# schematic.net
KiCad netlist of a schematic drawn in EasyEDA
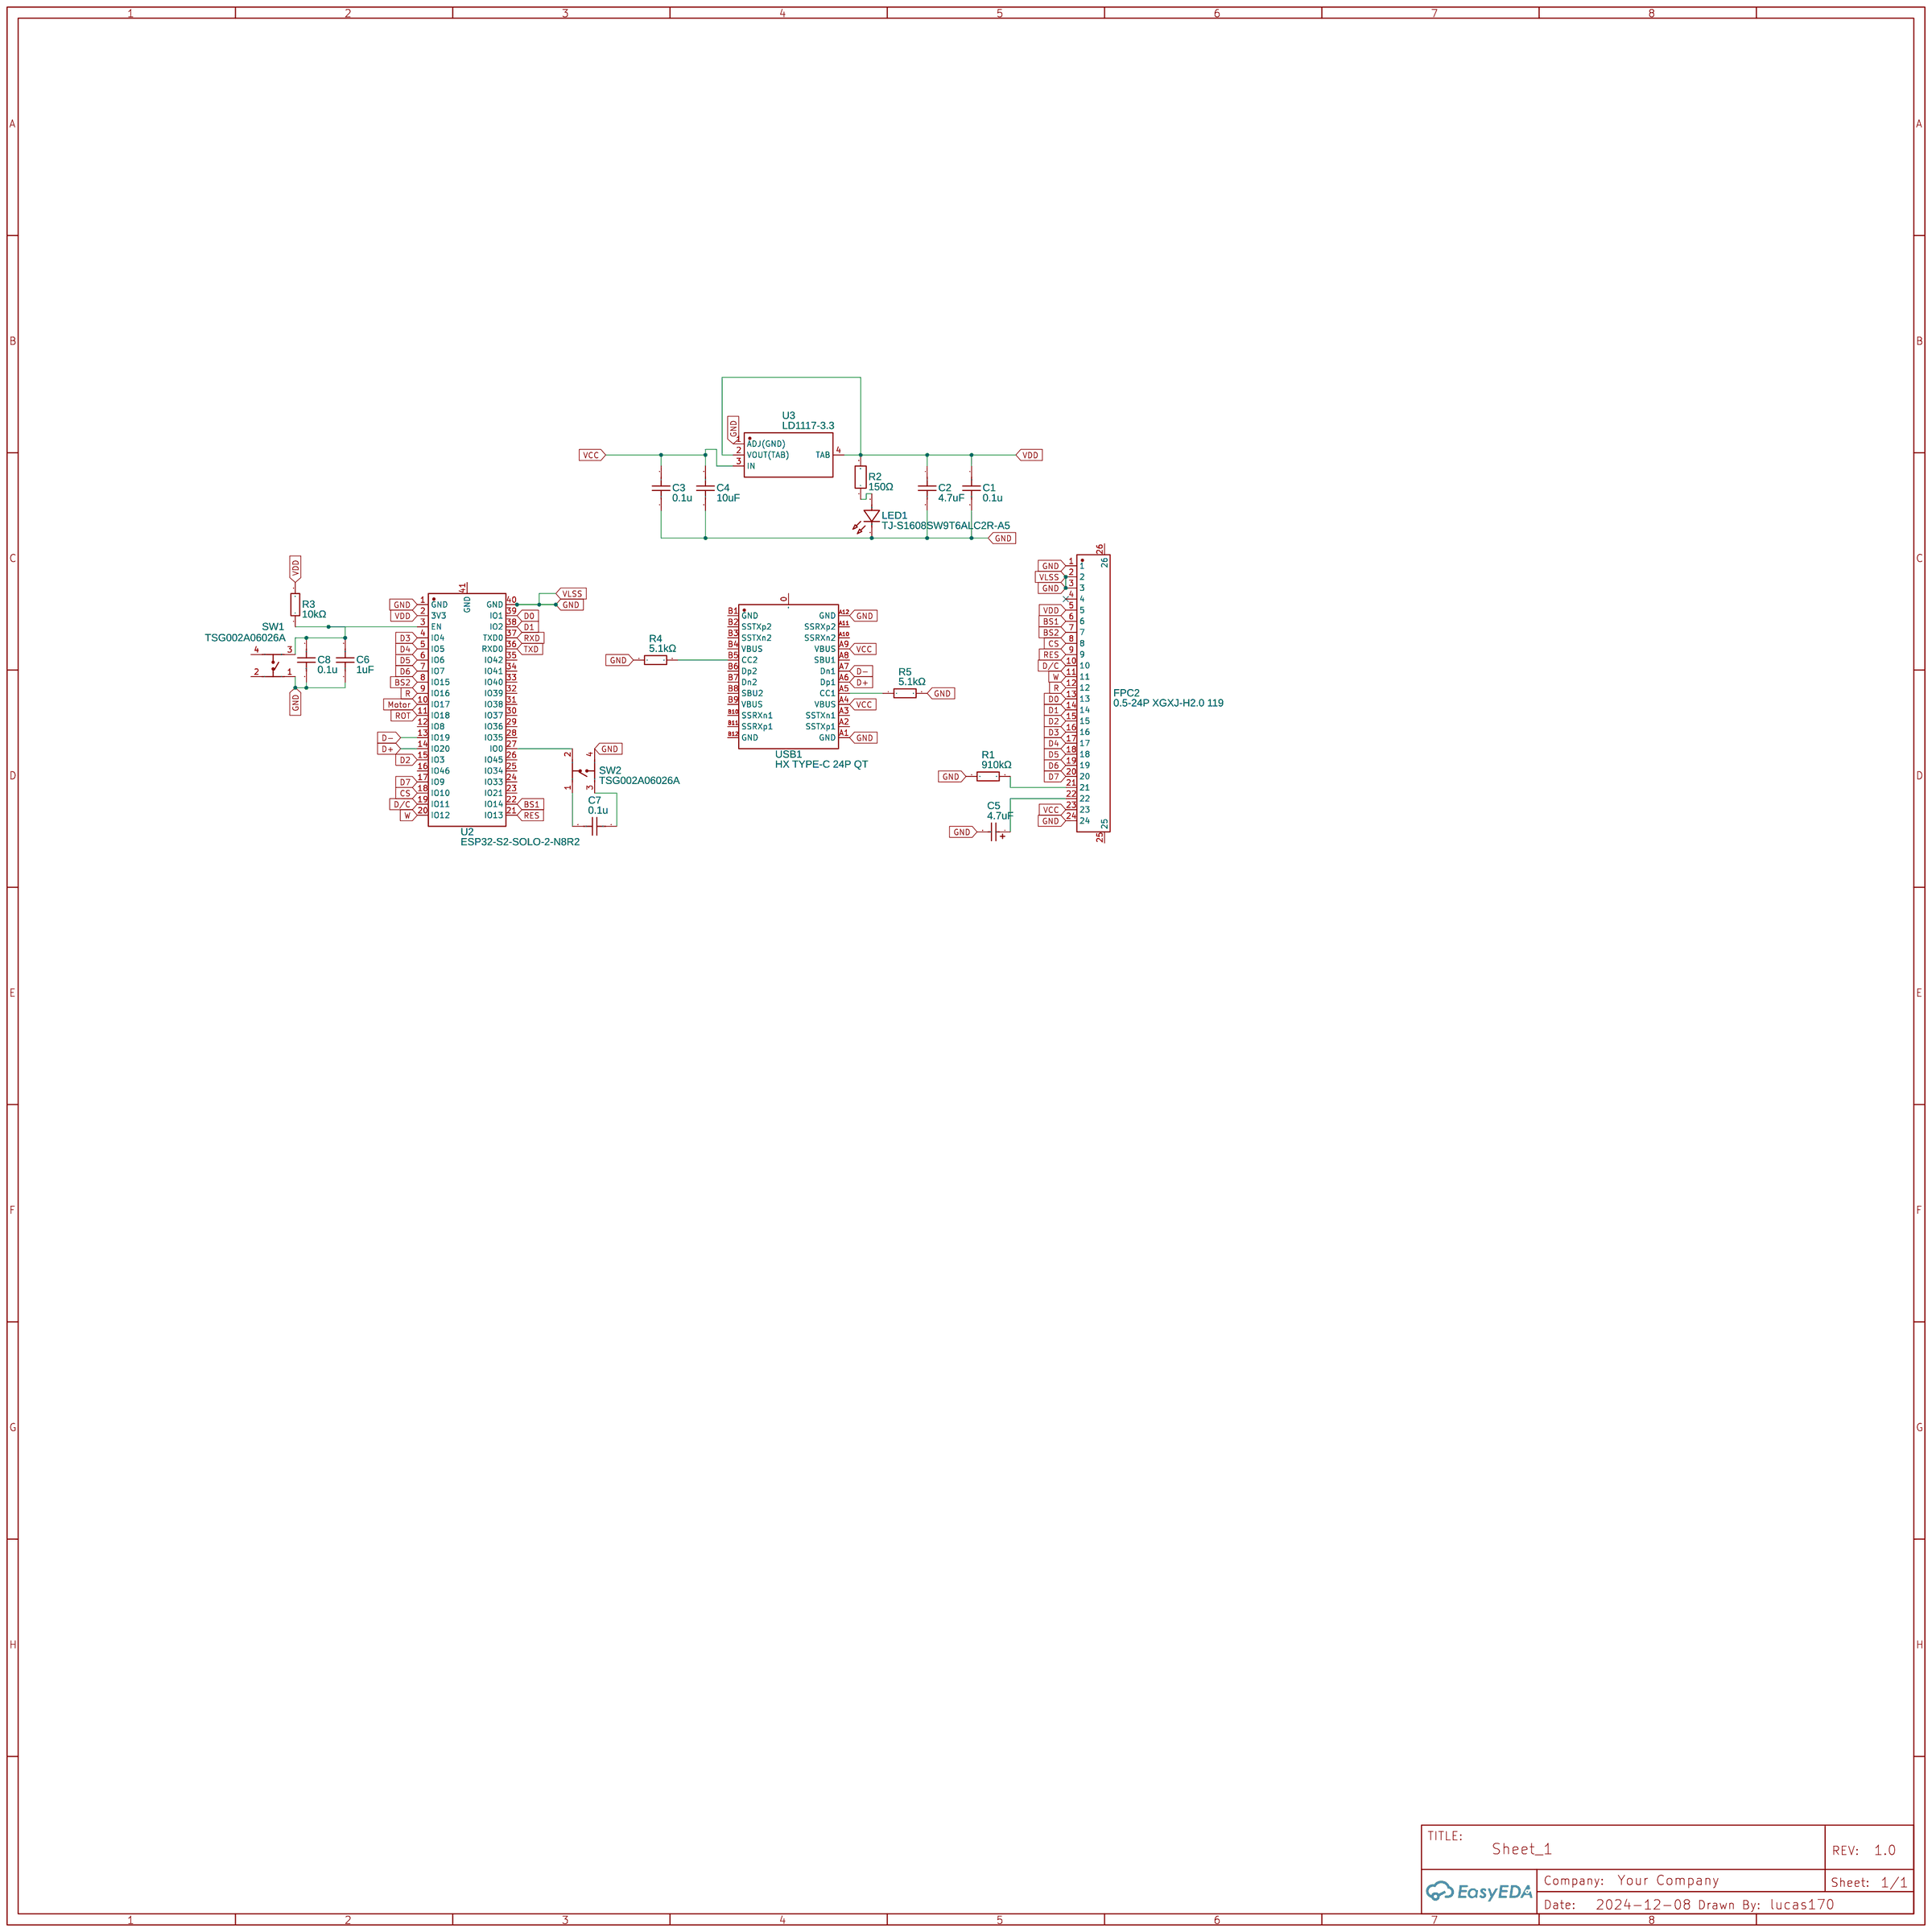
[diagram p0: schematic sheet]

(export (version "E")
  (design (tool "Eeschema 10.0.6"))
  (components
    (comp (ref "C1")
      (value "0.1u")
      (fields
        (field (name "Manufacturer Part") "CS1005X7R104K500NR")
        (field (name "Manufacturer") "Samwha Capacitor")
      )
      (libsource (lib "") (part "0.1u"))
    )
    (comp (ref "C2")
      (value "4.7uF")
      (fields
        (field (name "Manufacturer Part") "CS3216X7R475K500NRI")
        (field (name "Manufacturer") "SAMWHA(三和)")
      )
      (libsource (lib "") (part "CS3216X7R475K500NRI"))
    )
    (comp (ref "C3")
      (value "0.1u")
      (fields
        (field (name "Manufacturer Part") "CS1005X7R104K500NR")
        (field (name "Manufacturer") "Samwha Capacitor")
      )
      (libsource (lib "") (part "0.1u_1"))
    )
    (comp (ref "C4")
      (value "10uF")
      (fields
        (field (name "Manufacturer Part") "CS3225X7R106K500NRL")
        (field (name "Manufacturer") "SAMWHA(三和)")
      )
      (libsource (lib "") (part "CS3225X7R106K500NRL"))
    )
    (comp (ref "C5")
      (value "4.7uF")
      (fields (field (name "Manufacturer Part") "TAJA475K020RNJ") (field (name "Manufacturer") "Kyocera AVX"))
      (libsource (lib "") (part "TAJA475K020RNJ"))
    )
    (comp (ref "C6")
      (value "1uF")
      (fields
        (field (name "Manufacturer Part") "TCC0402X5R105M100AT")
        (field (name "Manufacturer") "CCTC(三环)")
      )
      (libsource (lib "") (part "TCC0402X5R105M100AT"))
    )
    (comp (ref "C7")
      (value "0.1u")
      (fields
        (field (name "Manufacturer Part") "CS1005X7R104K500NR")
        (field (name "Manufacturer") "Samwha Capacitor")
      )
      (libsource (lib "") (part "0.1u_2"))
    )
    (comp (ref "C8")
      (value "0.1u")
      (fields
        (field (name "Manufacturer Part") "CS1005X7R104K500NR")
        (field (name "Manufacturer") "Samwha Capacitor")
      )
      (libsource (lib "") (part "0.1u"))
    )
    (comp (ref "FPC2")
      (value "0.5-24P XGXJ-H2.0 119")
      (fields (field (name "Manufacturer") "SHOU HAN(首韩)"))
      (libsource (lib "") (part "0.5-24P XGXJ-H2.0 119"))
    )
    (comp (ref "LED1")
      (value "TJ-S1608SW9T6ALC2R-A5")
      (fields (field (name "Manufacturer") "TOGIALED(统佳)"))
      (libsource (lib "") (part "TJ-S1608SW9T6ALC2R-A5"))
    )
    (comp (ref "R1")
      (value "910kΩ")
      (fields
        (field (name "Manufacturer Part") "0805W8F9103T5E")
        (field (name "Manufacturer") "UNI-ROYAL(厚声)")
      )
      (libsource (lib "") (part "0805W8F9103T5E"))
    )
    (comp (ref "R2")
      (value "150Ω")
      (fields (field (name "Manufacturer Part") "PTFR0603B150RN9") (field (name "Manufacturer") "RESI(开步睿思)"))
      (libsource (lib "") (part "PTFR0603B150RN9"))
    )
    (comp (ref "R3")
      (value "10kΩ")
      (fields (field (name "Manufacturer Part") "RC0603FR-0710KL") (field (name "Manufacturer") "YAGEO(国巨)"))
      (libsource (lib "") (part "RC0603FR-0710KL"))
    )
    (comp (ref "R4")
      (value "5.1kΩ")
      (fields (field (name "Manufacturer Part") "RTT05512JTP") (field (name "Manufacturer") "RALEC(旺诠)"))
      (libsource (lib "") (part "RTT05512JTP"))
    )
    (comp (ref "R5")
      (value "5.1kΩ")
      (fields (field (name "Manufacturer Part") "RTT05512JTP") (field (name "Manufacturer") "RALEC(旺诠)"))
      (libsource (lib "") (part "RTT05512JTP"))
    )
    (comp (ref "SW1")
      (value "TSG002A06026A")
      (fields (field (name "Manufacturer") "BZCN(博众电气)"))
      (libsource (lib "") (part "TSG002A06026A"))
    )
    (comp (ref "SW2")
      (value "TSG002A06026A")
      (fields (field (name "Manufacturer") "BZCN(博众电气)"))
      (libsource (lib "") (part "TSG002A06026A_1"))
    )
    (comp (ref "U2") (value "ESP32-S2-SOLO-2-N8R2") (libsource (lib "") (part "ESP32-S2-SOLO-2-N8R2")))
    (comp (ref "U3")
      (value "LD1117-3.3")
      (fields (field (name "Manufacturer") "UMW(友台半导体)"))
      (libsource (lib "") (part "LD1117-3.3"))
    )
    (comp (ref "USB1")
      (value "HX TYPE-C 24P QT")
      (fields (field (name "Manufacturer") "hanxia(韩下)"))
      (libsource (lib "") (part "HX TYPE-C 24P QT"))
    )
  )
  (nets
    (net (code "1") (name "BS1") (class "Default")
      (node (ref "FPC2") (pin "6") (pinfunction "6_6") (pintype "unspecified"))
      (node (ref "U2") (pin "22") (pinfunction "IO14_22") (pintype "unspecified"))
    )
    (net (code "2") (name "BS2") (class "Default")
      (node (ref "FPC2") (pin "7") (pinfunction "7_7") (pintype "unspecified"))
      (node (ref "U2") (pin "8") (pinfunction "IO15_8") (pintype "unspecified"))
    )
    (net (code "3") (name "CS") (class "Default")
      (node (ref "FPC2") (pin "8") (pinfunction "8_8") (pintype "unspecified"))
      (node (ref "U2") (pin "18") (pinfunction "IO10_18") (pintype "unspecified"))
    )
    (net (code "4") (name "D+") (class "Default")
      (node (ref "U2") (pin "14") (pinfunction "IO20_14") (pintype "unspecified"))
      (node (ref "USB1") (pin "A6") (pinfunction "Dp1_A6") (pintype "unspecified"))
    )
    (net (code "5") (name "D-") (class "Default")
      (node (ref "U2") (pin "13") (pinfunction "IO19_13") (pintype "unspecified"))
      (node (ref "USB1") (pin "A7") (pinfunction "Dn1_A7") (pintype "unspecified"))
    )
    (net (code "6") (name "D0") (class "Default")
      (node (ref "FPC2") (pin "13") (pinfunction "13_13") (pintype "unspecified"))
      (node (ref "U2") (pin "39") (pinfunction "IO1_39") (pintype "unspecified"))
    )
    (net (code "7") (name "D1") (class "Default")
      (node (ref "FPC2") (pin "14") (pinfunction "14_14") (pintype "unspecified"))
      (node (ref "U2") (pin "38") (pinfunction "IO2_38") (pintype "unspecified"))
    )
    (net (code "8") (name "D2") (class "Default")
      (node (ref "FPC2") (pin "15") (pinfunction "15_15") (pintype "unspecified"))
      (node (ref "U2") (pin "15") (pinfunction "IO3_15") (pintype "unspecified"))
    )
    (net (code "9") (name "D3") (class "Default")
      (node (ref "FPC2") (pin "16") (pinfunction "16_16") (pintype "unspecified"))
      (node (ref "U2") (pin "4") (pinfunction "IO4_4") (pintype "unspecified"))
    )
    (net (code "10") (name "D4") (class "Default")
      (node (ref "FPC2") (pin "17") (pinfunction "17_17") (pintype "unspecified"))
      (node (ref "U2") (pin "5") (pinfunction "IO5_5") (pintype "unspecified"))
    )
    (net (code "11") (name "D5") (class "Default")
      (node (ref "FPC2") (pin "18") (pinfunction "18_18") (pintype "unspecified"))
      (node (ref "U2") (pin "6") (pinfunction "IO6_6") (pintype "unspecified"))
    )
    (net (code "12") (name "D6") (class "Default")
      (node (ref "FPC2") (pin "19") (pinfunction "19_19") (pintype "unspecified"))
      (node (ref "U2") (pin "7") (pinfunction "IO7_7") (pintype "unspecified"))
    )
    (net (code "13") (name "D7") (class "Default")
      (node (ref "FPC2") (pin "20") (pinfunction "20_20") (pintype "unspecified"))
      (node (ref "U2") (pin "17") (pinfunction "IO9_17") (pintype "unspecified"))
    )
    (net (code "14") (name "D{slash}C") (class "Default")
      (node (ref "FPC2") (pin "10") (pinfunction "10_10") (pintype "unspecified"))
      (node (ref "U2") (pin "19") (pinfunction "IO11_19") (pintype "unspecified"))
    )
    (net (code "15") (name "GND") (class "Default")
      (node (ref "C1") (pin "2") (pinfunction "2_2") (pintype "unspecified"))
      (node (ref "C2") (pin "2") (pinfunction "2_2") (pintype "unspecified"))
      (node (ref "C3") (pin "1") (pinfunction "1_1") (pintype "unspecified"))
      (node (ref "C4") (pin "1") (pinfunction "1_1") (pintype "unspecified"))
      (node (ref "C5") (pin "2") (pinfunction "2_2") (pintype "input"))
      (node (ref "C6") (pin "1") (pinfunction "1_1") (pintype "unspecified"))
      (node (ref "C8") (pin "2") (pinfunction "2_2") (pintype "unspecified"))
      (node (ref "FPC2") (pin "1") (pinfunction "1_1") (pintype "unspecified"))
      (node (ref "FPC2") (pin "2") (pinfunction "2_2") (pintype "unspecified"))
      (node (ref "FPC2") (pin "24") (pinfunction "24_24") (pintype "unspecified"))
      (node (ref "FPC2") (pin "3") (pinfunction "3_3") (pintype "unspecified"))
      (node (ref "LED1") (pin "1") (pinfunction "K_1") (pintype "unspecified"))
      (node (ref "R1") (pin "1") (pinfunction "1_1") (pintype "input"))
      (node (ref "R4") (pin "1") (pinfunction "1_1") (pintype "input"))
      (node (ref "R5") (pin "2") (pinfunction "2_2") (pintype "input"))
      (node (ref "SW1") (pin "1") (pinfunction "1_1") (pintype "unspecified"))
      (node (ref "SW2") (pin "4") (pinfunction "4_4") (pintype "unspecified"))
      (node (ref "U2") (pin "1") (pinfunction "GND_1") (pintype "unspecified"))
      (node (ref "U2") (pin "40") (pinfunction "GND_40") (pintype "unspecified"))
      (node (ref "U3") (pin "1") (pinfunction "ADJ(GND)_1") (pintype "unspecified"))
      (node (ref "USB1") (pin "A1") (pinfunction "GND_A1") (pintype "unspecified"))
      (node (ref "USB1") (pin "A12") (pinfunction "GND_A12") (pintype "unspecified"))
    )
    (net (code "16") (name "Motor") (class "Default")
      (node (ref "U2") (pin "10") (pinfunction "IO17_10") (pintype "unspecified"))
    )
    (net (code "17") (name "Net-(C5-Pad1)") (class "Default")
      (node (ref "C5") (pin "1") (pinfunction "1_1") (pintype "input"))
      (node (ref "FPC2") (pin "22") (pinfunction "22_22") (pintype "unspecified"))
    )
    (net (code "18") (name "Net-(C7-Pad1)") (class "Default")
      (node (ref "C7") (pin "1") (pinfunction "1_1") (pintype "unspecified"))
      (node (ref "SW2") (pin "3") (pinfunction "3_3") (pintype "unspecified"))
    )
    (net (code "19") (name "Net-(C7-Pad2)") (class "Default")
      (node (ref "C7") (pin "2") (pinfunction "2_2") (pintype "unspecified"))
      (node (ref "SW2") (pin "1") (pinfunction "1_1") (pintype "unspecified"))
    )
    (net (code "20") (name "Net-(FPC2-Pad21)") (class "Default")
      (node (ref "FPC2") (pin "21") (pinfunction "21_21") (pintype "unspecified"))
      (node (ref "R1") (pin "2") (pinfunction "2_2") (pintype "input"))
    )
    (net (code "21") (name "Net-(LED1-A)") (class "Default")
      (node (ref "LED1") (pin "2") (pinfunction "A_2") (pintype "unspecified"))
      (node (ref "R2") (pin "1") (pinfunction "1_1") (pintype "unspecified"))
    )
    (net (code "22") (name "Net-(U2-EN)") (class "Default")
      (node (ref "C6") (pin "2") (pinfunction "2_2") (pintype "unspecified"))
      (node (ref "C8") (pin "1") (pinfunction "1_1") (pintype "unspecified"))
      (node (ref "R3") (pin "1") (pinfunction "1_1") (pintype "input"))
      (node (ref "SW1") (pin "3") (pinfunction "3_3") (pintype "unspecified"))
      (node (ref "U2") (pin "3") (pinfunction "EN_3") (pintype "unspecified"))
    )
    (net (code "23") (name "Net-(U2-IO0)") (class "Default")
      (node (ref "SW2") (pin "2") (pinfunction "2_2") (pintype "unspecified"))
      (node (ref "U2") (pin "27") (pinfunction "IO0_27") (pintype "unspecified"))
    )
    (net (code "24") (name "Net-(USB1-CC1)") (class "Default")
      (node (ref "R5") (pin "1") (pinfunction "1_1") (pintype "input"))
      (node (ref "USB1") (pin "A5") (pinfunction "CC1_A5") (pintype "unspecified"))
    )
    (net (code "25") (name "Net-(USB1-CC2)") (class "Default")
      (node (ref "R4") (pin "2") (pinfunction "2_2") (pintype "input"))
      (node (ref "USB1") (pin "B5") (pinfunction "CC2_B5") (pintype "unspecified"))
    )
    (net (code "26") (name "R") (class "Default")
      (node (ref "FPC2") (pin "12") (pinfunction "12_12") (pintype "unspecified"))
      (node (ref "U2") (pin "9") (pinfunction "IO16_9") (pintype "unspecified"))
    )
    (net (code "27") (name "RES") (class "Default")
      (node (ref "FPC2") (pin "9") (pinfunction "9_9") (pintype "unspecified"))
      (node (ref "U2") (pin "21") (pinfunction "IO13_21") (pintype "unspecified"))
    )
    (net (code "28") (name "ROT") (class "Default")
      (node (ref "U2") (pin "11") (pinfunction "IO18_11") (pintype "unspecified"))
    )
    (net (code "29") (name "RXD") (class "Default")
      (node (ref "U2") (pin "37") (pinfunction "TXD0_37") (pintype "unspecified"))
    )
    (net (code "30") (name "TXD") (class "Default")
      (node (ref "U2") (pin "36") (pinfunction "RXD0_36") (pintype "unspecified"))
    )
    (net (code "31") (name "VCC") (class "Default")
      (node (ref "C3") (pin "2") (pinfunction "2_2") (pintype "unspecified"))
      (node (ref "C4") (pin "2") (pinfunction "2_2") (pintype "unspecified"))
      (node (ref "FPC2") (pin "23") (pinfunction "23_23") (pintype "unspecified"))
      (node (ref "U3") (pin "3") (pinfunction "IN_3") (pintype "unspecified"))
      (node (ref "USB1") (pin "A4") (pinfunction "VBUS_A4") (pintype "unspecified"))
      (node (ref "USB1") (pin "A9") (pinfunction "VBUS_A9") (pintype "unspecified"))
    )
    (net (code "32") (name "VDD") (class "Default")
      (node (ref "C1") (pin "1") (pinfunction "1_1") (pintype "unspecified"))
      (node (ref "C2") (pin "1") (pinfunction "1_1") (pintype "unspecified"))
      (node (ref "FPC2") (pin "5") (pinfunction "5_5") (pintype "unspecified"))
      (node (ref "R2") (pin "2") (pinfunction "2_2") (pintype "unspecified"))
      (node (ref "R3") (pin "2") (pinfunction "2_2") (pintype "input"))
      (node (ref "U2") (pin "2") (pinfunction "3V3_2") (pintype "unspecified"))
      (node (ref "U3") (pin "2") (pinfunction "VOUT(TAB)_2") (pintype "unspecified"))
      (node (ref "U3") (pin "4") (pinfunction "TAB_4") (pintype "unspecified"))
    )
    (net (code "33") (name "W") (class "Default")
      (node (ref "FPC2") (pin "11") (pinfunction "11_11") (pintype "unspecified"))
      (node (ref "U2") (pin "20") (pinfunction "IO12_20") (pintype "unspecified"))
    )
    (net (code "34") (name "unconnected-(FPC2-Pad4)") (class "Default")
      (node (ref "FPC2") (pin "4") (pinfunction "4_4") (pintype "unspecified+no_connect"))
    )
    (net (code "35") (name "unconnected-(FPC2-Pad25)") (class "Default")
      (node (ref "FPC2") (pin "25") (pinfunction "25_25") (pintype "unspecified"))
    )
    (net (code "36") (name "unconnected-(FPC2-Pad26)") (class "Default")
      (node (ref "FPC2") (pin "26") (pinfunction "26_26") (pintype "unspecified"))
    )
    (net (code "37") (name "unconnected-(SW1-Pad2)") (class "Default")
      (node (ref "SW1") (pin "2") (pinfunction "2_2") (pintype "unspecified"))
    )
    (net (code "38") (name "unconnected-(SW1-Pad4)") (class "Default")
      (node (ref "SW1") (pin "4") (pinfunction "4_4") (pintype "unspecified"))
    )
    (net (code "39") (name "unconnected-(U2-GND-Pad41)") (class "Default")
      (node (ref "U2") (pin "41") (pinfunction "GND_41") (pintype "unspecified"))
    )
    (net (code "40") (name "unconnected-(U2-IO8-Pad12)") (class "Default")
      (node (ref "U2") (pin "12") (pinfunction "IO8_12") (pintype "unspecified"))
    )
    (net (code "41") (name "unconnected-(U2-IO21-Pad23)") (class "Default")
      (node (ref "U2") (pin "23") (pinfunction "IO21_23") (pintype "unspecified"))
    )
    (net (code "42") (name "unconnected-(U2-IO33-Pad24)") (class "Default")
      (node (ref "U2") (pin "24") (pinfunction "IO33_24") (pintype "unspecified"))
    )
    (net (code "43") (name "unconnected-(U2-IO34-Pad25)") (class "Default")
      (node (ref "U2") (pin "25") (pinfunction "IO34_25") (pintype "unspecified"))
    )
    (net (code "44") (name "unconnected-(U2-IO35-Pad28)") (class "Default")
      (node (ref "U2") (pin "28") (pinfunction "IO35_28") (pintype "unspecified"))
    )
    (net (code "45") (name "unconnected-(U2-IO36-Pad29)") (class "Default")
      (node (ref "U2") (pin "29") (pinfunction "IO36_29") (pintype "unspecified"))
    )
    (net (code "46") (name "unconnected-(U2-IO37-Pad30)") (class "Default")
      (node (ref "U2") (pin "30") (pinfunction "IO37_30") (pintype "unspecified"))
    )
    (net (code "47") (name "unconnected-(U2-IO38-Pad31)") (class "Default")
      (node (ref "U2") (pin "31") (pinfunction "IO38_31") (pintype "unspecified"))
    )
    (net (code "48") (name "unconnected-(U2-IO39-Pad32)") (class "Default")
      (node (ref "U2") (pin "32") (pinfunction "IO39_32") (pintype "unspecified"))
    )
    (net (code "49") (name "unconnected-(U2-IO40-Pad33)") (class "Default")
      (node (ref "U2") (pin "33") (pinfunction "IO40_33") (pintype "unspecified"))
    )
    (net (code "50") (name "unconnected-(U2-IO41-Pad34)") (class "Default")
      (node (ref "U2") (pin "34") (pinfunction "IO41_34") (pintype "unspecified"))
    )
    (net (code "51") (name "unconnected-(U2-IO42-Pad35)") (class "Default")
      (node (ref "U2") (pin "35") (pinfunction "IO42_35") (pintype "unspecified"))
    )
    (net (code "52") (name "unconnected-(U2-IO45-Pad26)") (class "Default")
      (node (ref "U2") (pin "26") (pinfunction "IO45_26") (pintype "unspecified"))
    )
    (net (code "53") (name "unconnected-(U2-IO46-Pad16)") (class "Default")
      (node (ref "U2") (pin "16") (pinfunction "IO46_16") (pintype "unspecified"))
    )
    (net (code "54") (name "unconnected-(USB1-Dn2-PadB7)") (class "Default")
      (node (ref "USB1") (pin "B7") (pinfunction "Dn2_B7") (pintype "unspecified"))
    )
    (net (code "55") (name "unconnected-(USB1-Dp2-PadB6)") (class "Default")
      (node (ref "USB1") (pin "B6") (pinfunction "Dp2_B6") (pintype "unspecified"))
    )
    (net (code "56") (name "unconnected-(USB1-GND-PadB1)") (class "Default")
      (node (ref "USB1") (pin "B1") (pinfunction "GND_B1") (pintype "unspecified"))
    )
    (net (code "57") (name "unconnected-(USB1-GND-PadB12)") (class "Default")
      (node (ref "USB1") (pin "B12") (pinfunction "GND_B12") (pintype "unspecified"))
    )
    (net (code "58") (name "unconnected-(USB1-SBU1-PadA8)") (class "Default")
      (node (ref "USB1") (pin "A8") (pinfunction "SBU1_A8") (pintype "unspecified"))
    )
    (net (code "59") (name "unconnected-(USB1-SBU2-PadB8)") (class "Default")
      (node (ref "USB1") (pin "B8") (pinfunction "SBU2_B8") (pintype "unspecified"))
    )
    (net (code "60") (name "unconnected-(USB1-SHEELD-Pad0)") (class "Default")
      (node (ref "USB1") (pin "0") (pinfunction "SHEELD_0") (pintype "unspecified"))
    )
    (net (code "61") (name "unconnected-(USB1-SSRXn1-PadB10)") (class "Default")
      (node (ref "USB1") (pin "B10") (pinfunction "SSRXn1_B10") (pintype "unspecified"))
    )
    (net (code "62") (name "unconnected-(USB1-SSRXn2-PadA10)") (class "Default")
      (node (ref "USB1") (pin "A10") (pinfunction "SSRXn2_A10") (pintype "unspecified"))
    )
    (net (code "63") (name "unconnected-(USB1-SSRXp1-PadB11)") (class "Default")
      (node (ref "USB1") (pin "B11") (pinfunction "SSRXp1_B11") (pintype "unspecified"))
    )
    (net (code "64") (name "unconnected-(USB1-SSRXp2-PadA11)") (class "Default")
      (node (ref "USB1") (pin "A11") (pinfunction "SSRXp2_A11") (pintype "unspecified"))
    )
    (net (code "65") (name "unconnected-(USB1-SSTXn1-PadA3)") (class "Default")
      (node (ref "USB1") (pin "A3") (pinfunction "SSTXn1_A3") (pintype "unspecified"))
    )
    (net (code "66") (name "unconnected-(USB1-SSTXn2-PadB3)") (class "Default")
      (node (ref "USB1") (pin "B3") (pinfunction "SSTXn2_B3") (pintype "unspecified"))
    )
    (net (code "67") (name "unconnected-(USB1-SSTXp1-PadA2)") (class "Default")
      (node (ref "USB1") (pin "A2") (pinfunction "SSTXp1_A2") (pintype "unspecified"))
    )
    (net (code "68") (name "unconnected-(USB1-SSTXp2-PadB2)") (class "Default")
      (node (ref "USB1") (pin "B2") (pinfunction "SSTXp2_B2") (pintype "unspecified"))
    )
    (net (code "69") (name "unconnected-(USB1-VBUS-PadB4)") (class "Default")
      (node (ref "USB1") (pin "B4") (pinfunction "VBUS_B4") (pintype "unspecified"))
    )
    (net (code "70") (name "unconnected-(USB1-VBUS-PadB9)") (class "Default")
      (node (ref "USB1") (pin "B9") (pinfunction "VBUS_B9") (pintype "unspecified"))
    )
  )
)
